# Generator40.net
KiCad netlist of a schematic drawn in Altium Designer
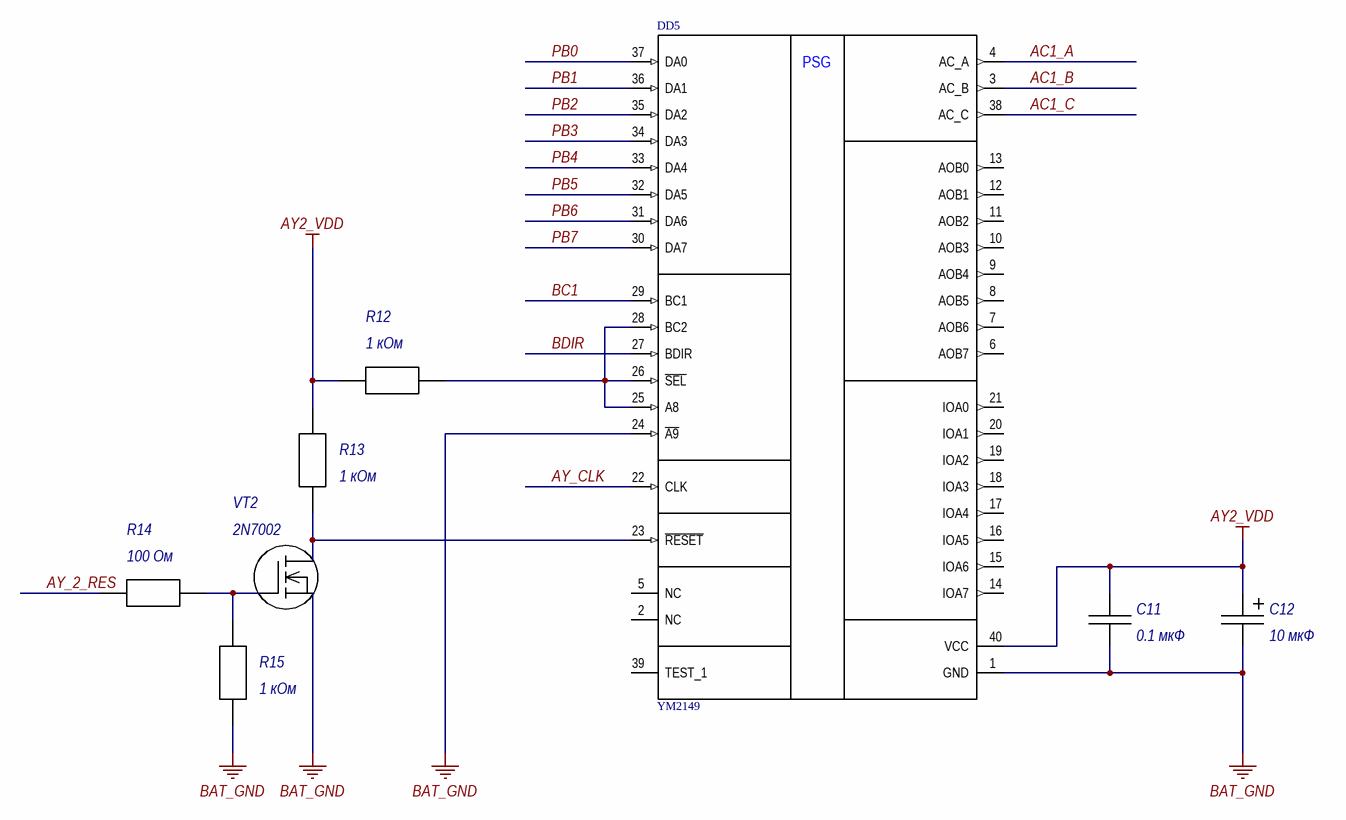
[diagram p0: Generator40.SchDoc]

(export (version "E")
  (design (tool "Eeschema 10.0.6"))
  (components
    (comp (ref "C11")
      (value "0.1 мкФ")
      (footprint "C 1206")
      (description "SMD Capacitor 1206")
      (fields
        (field (name "TOLERANCE") "/Укажите допуск в процентах/")
        (field (name "MANUFACTURER") "/Укажите компанию-производителя/")
      )
      (libsource (lib "my_lib") (part "CAP 1206"))
    )
    (comp (ref "C12")
      (value "10 мкФ")
      (footprint "C TAN_A")
      (description "SMD Tantalium Capacitor A")
      (libsource (lib "my_lib") (part "CAP TAN_A"))
    )
    (comp (ref "DD5")
      (value "YM2149")
      (footprint "DIP40_PLUS_MCU")
      (libsource (lib "my_lib") (part "YM2149"))
    )
    (comp (ref "R12") (value "1 кОм") (footprint "RES 0805") (libsource (lib "my_lib") (part "RES 0805")))
    (comp (ref "R13") (value "1 кОм") (footprint "RES 0805") (libsource (lib "my_lib") (part "RES 0805")))
    (comp (ref "R14") (value "100 Ом") (footprint "RES 0805") (libsource (lib "my_lib") (part "RES 0805")))
    (comp (ref "R15") (value "1 кОм") (footprint "RES 0805") (libsource (lib "my_lib") (part "RES 0805")))
    (comp (ref "VT2")
      (value "2N7002")
      (footprint "SOT-23")
      (description "60 V, 300 mA N-channel Trench MOSFET")
      (fields (field (name "MANUFACTURER") "NXP"))
      (libsource (lib "my_lib") (part "2N7002"))
    )
  )
  (nets
    (net (code "1") (name "/AC1_A") (class "Default")
      (node (ref "DD5") (pin "4") (pinfunction "AC_A_4") (pintype "output"))
    )
    (net (code "2") (name "/AC1_B") (class "Default")
      (node (ref "DD5") (pin "3") (pinfunction "AC_B_3") (pintype "output"))
    )
    (net (code "3") (name "/AC1_C") (class "Default")
      (node (ref "DD5") (pin "38") (pinfunction "AC_C_38") (pintype "output"))
    )
    (net (code "4") (name "/AY_2_RES") (class "Default")
      (node (ref "R14") (pin "1") (pinfunction "1_1") (pintype "passive"))
    )
    (net (code "5") (name "/AY_CLK") (class "Default")
      (node (ref "DD5") (pin "22") (pinfunction "CLK_22") (pintype "input"))
    )
    (net (code "6") (name "/BC1") (class "Default")
      (node (ref "DD5") (pin "29") (pinfunction "BC1_29") (pintype "input"))
    )
    (net (code "7") (name "/BDIR") (class "Default")
      (node (ref "DD5") (pin "27") (pinfunction "BDIR_27") (pintype "input"))
    )
    (net (code "8") (name "/PB0") (class "Default")
      (node (ref "DD5") (pin "37") (pinfunction "DA0_37") (pintype "input"))
    )
    (net (code "9") (name "/PB1") (class "Default")
      (node (ref "DD5") (pin "36") (pinfunction "DA1_36") (pintype "input"))
    )
    (net (code "10") (name "/PB2") (class "Default")
      (node (ref "DD5") (pin "35") (pinfunction "DA2_35") (pintype "input"))
    )
    (net (code "11") (name "/PB3") (class "Default")
      (node (ref "DD5") (pin "34") (pinfunction "DA3_34") (pintype "input"))
    )
    (net (code "12") (name "/PB4") (class "Default")
      (node (ref "DD5") (pin "33") (pinfunction "DA4_33") (pintype "input"))
    )
    (net (code "13") (name "/PB5") (class "Default")
      (node (ref "DD5") (pin "32") (pinfunction "DA5_32") (pintype "input"))
    )
    (net (code "14") (name "/PB6") (class "Default")
      (node (ref "DD5") (pin "31") (pinfunction "DA6_31") (pintype "input"))
    )
    (net (code "15") (name "/PB7") (class "Default")
      (node (ref "DD5") (pin "30") (pinfunction "DA7_30") (pintype "input"))
    )
    (net (code "16") (name "AY2_VDD") (class "Default")
      (node (ref "C11") (pin "1") (pinfunction "1_1") (pintype "passive"))
      (node (ref "C12") (pin "1") (pinfunction "1_1") (pintype "passive"))
      (node (ref "DD5") (pin "40") (pinfunction "VCC_40") (pintype "power_in"))
      (node (ref "R12") (pin "2") (pinfunction "2_2") (pintype "passive"))
      (node (ref "R13") (pin "2") (pinfunction "2_2") (pintype "passive"))
    )
    (net (code "17") (name "BAT_GND") (class "Default")
      (node (ref "C11") (pin "2") (pinfunction "2_2") (pintype "passive"))
      (node (ref "C12") (pin "2") (pinfunction "2_2") (pintype "passive"))
      (node (ref "DD5") (pin "1") (pinfunction "GND_1") (pintype "power_in"))
      (node (ref "DD5") (pin "24") (pinfunction "~{A9}_24") (pintype "input"))
      (node (ref "R15") (pin "1") (pinfunction "1_1") (pintype "passive"))
      (node (ref "VT2") (pin "2") (pinfunction "S_2") (pintype "passive"))
    )
    (net (code "18") (name "Net-(DD5-A8)") (class "Default")
      (node (ref "DD5") (pin "25") (pinfunction "A8_25") (pintype "input"))
      (node (ref "DD5") (pin "26") (pinfunction "~{SEL}_26") (pintype "input"))
      (node (ref "DD5") (pin "28") (pinfunction "BC2_28") (pintype "input"))
      (node (ref "R12") (pin "1") (pinfunction "1_1") (pintype "passive"))
    )
    (net (code "19") (name "Net-(DD5-~{RESET})") (class "Default")
      (node (ref "DD5") (pin "23") (pinfunction "~{RESET}_23") (pintype "input"))
      (node (ref "R13") (pin "1") (pinfunction "1_1") (pintype "passive"))
      (node (ref "VT2") (pin "3") (pinfunction "D_3") (pintype "passive"))
    )
    (net (code "20") (name "Net-(VT2-G)") (class "Default")
      (node (ref "R14") (pin "2") (pinfunction "2_2") (pintype "passive"))
      (node (ref "R15") (pin "2") (pinfunction "2_2") (pintype "passive"))
      (node (ref "VT2") (pin "1") (pinfunction "G_1") (pintype "passive"))
    )
    (net (code "21") (name "unconnected-(DD5-AOB0-Pad13)") (class "Default")
      (node (ref "DD5") (pin "13") (pinfunction "AOB0_13") (pintype "output"))
    )
    (net (code "22") (name "unconnected-(DD5-AOB1-Pad12)") (class "Default")
      (node (ref "DD5") (pin "12") (pinfunction "AOB1_12") (pintype "output"))
    )
    (net (code "23") (name "unconnected-(DD5-AOB2-Pad11)") (class "Default")
      (node (ref "DD5") (pin "11") (pinfunction "AOB2_11") (pintype "output"))
    )
    (net (code "24") (name "unconnected-(DD5-AOB3-Pad10)") (class "Default")
      (node (ref "DD5") (pin "10") (pinfunction "AOB3_10") (pintype "output"))
    )
    (net (code "25") (name "unconnected-(DD5-AOB4-Pad9)") (class "Default")
      (node (ref "DD5") (pin "9") (pinfunction "AOB4_9") (pintype "output"))
    )
    (net (code "26") (name "unconnected-(DD5-AOB5-Pad8)") (class "Default")
      (node (ref "DD5") (pin "8") (pinfunction "AOB5_8") (pintype "output"))
    )
    (net (code "27") (name "unconnected-(DD5-AOB6-Pad7)") (class "Default")
      (node (ref "DD5") (pin "7") (pinfunction "AOB6_7") (pintype "output"))
    )
    (net (code "28") (name "unconnected-(DD5-AOB7-Pad6)") (class "Default")
      (node (ref "DD5") (pin "6") (pinfunction "AOB7_6") (pintype "output"))
    )
    (net (code "29") (name "unconnected-(DD5-IOA0-Pad21)") (class "Default")
      (node (ref "DD5") (pin "21") (pinfunction "IOA0_21") (pintype "output"))
    )
    (net (code "30") (name "unconnected-(DD5-IOA1-Pad20)") (class "Default")
      (node (ref "DD5") (pin "20") (pinfunction "IOA1_20") (pintype "output"))
    )
    (net (code "31") (name "unconnected-(DD5-IOA2-Pad19)") (class "Default")
      (node (ref "DD5") (pin "19") (pinfunction "IOA2_19") (pintype "output"))
    )
    (net (code "32") (name "unconnected-(DD5-IOA3-Pad18)") (class "Default")
      (node (ref "DD5") (pin "18") (pinfunction "IOA3_18") (pintype "output"))
    )
    (net (code "33") (name "unconnected-(DD5-IOA4-Pad17)") (class "Default")
      (node (ref "DD5") (pin "17") (pinfunction "IOA4_17") (pintype "output"))
    )
    (net (code "34") (name "unconnected-(DD5-IOA5-Pad16)") (class "Default")
      (node (ref "DD5") (pin "16") (pinfunction "IOA5_16") (pintype "output"))
    )
    (net (code "35") (name "unconnected-(DD5-IOA6-Pad15)") (class "Default")
      (node (ref "DD5") (pin "15") (pinfunction "IOA6_15") (pintype "output"))
    )
    (net (code "36") (name "unconnected-(DD5-IOA7-Pad14)") (class "Default")
      (node (ref "DD5") (pin "14") (pinfunction "IOA7_14") (pintype "output"))
    )
    (net (code "37") (name "unconnected-(DD5-NC-Pad2)") (class "Default")
      (node (ref "DD5") (pin "2") (pinfunction "NC_2") (pintype "passive"))
    )
    (net (code "38") (name "unconnected-(DD5-NC-Pad5)") (class "Default")
      (node (ref "DD5") (pin "5") (pinfunction "NC_5") (pintype "passive"))
    )
    (net (code "39") (name "unconnected-(DD5-TEST_1-Pad39)") (class "Default")
      (node (ref "DD5") (pin "39") (pinfunction "TEST_1_39") (pintype "passive"))
    )
  )
)
